# BluetoothMainBoard.net
KiCad netlist of a schematic drawn in EAGLE
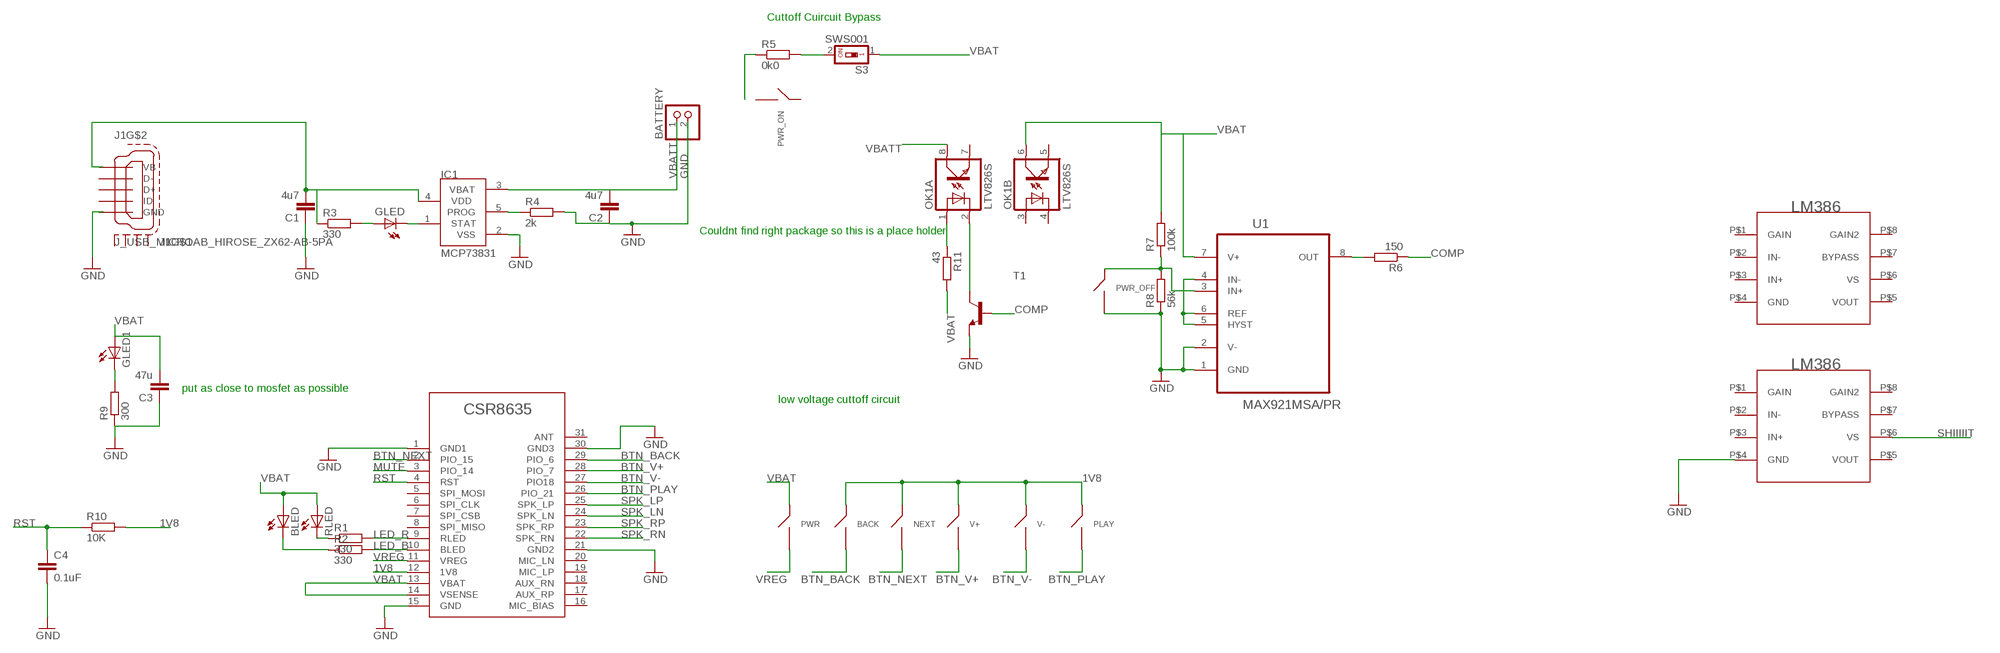
[diagram p0: schematic, sheet 1]

(export (version "E")
  (design (tool "Eeschema 10.0.6"))
  (components
    (comp (ref "BACK")
      (value "TACTILE")
      (footprint "eagle-import:DTSM31N")
      (libsource (lib "eagle-import") (part "TACTILE"))
    )
    (comp (ref "BATTERY")
      (value "PINHD-1X2")
      (footprint "eagle-import:1X02")
      (libsource (lib "eagle-import") (part "PINHD-1X2"))
    )
    (comp (ref "BLED")
      (value "LEDCHIPLED_1206")
      (footprint "eagle-import:CHIPLED_1206")
      (libsource (lib "eagle-import") (part "LEDCHIPLED_1206"))
    )
    (comp (ref "C1")
      (value "4u7")
      (footprint "eagle-import:C0805")
      (libsource (lib "eagle-import") (part "C-EUC0805"))
    )
    (comp (ref "C2")
      (value "4u7")
      (footprint "eagle-import:C0805")
      (libsource (lib "eagle-import") (part "C-EUC0805"))
    )
    (comp (ref "C3")
      (value "47u")
      (footprint "eagle-import:C0805")
      (libsource (lib "eagle-import") (part "C-EUC0805"))
    )
    (comp (ref "C4")
      (value "0.1uF")
      (footprint "eagle-import:C0805")
      (libsource (lib "eagle-import") (part "C-EUC0805"))
    )
    (comp (ref "GLED")
      (value "LEDCHIP-LED0805")
      (footprint "eagle-import:CHIP-LED0805")
      (libsource (lib "eagle-import") (part "led_LEDCHIP-LED0805"))
    )
    (comp (ref "GLED1")
      (value "LEDCHIP-LED0805")
      (footprint "eagle-import:CHIP-LED0805")
      (libsource (lib "eagle-import") (part "led_LEDCHIP-LED0805"))
    )
    (comp (ref "IC1")
      (value "MCP73831")
      (footprint "eagle-import:SOT23-5L")
      (libsource (lib "eagle-import") (part "MCP73831"))
    )
    (comp (ref "J1")
      (value "J_USB_MICROAB_HIROSE_ZX62-AB-5PA")
      (footprint "eagle-import:J_USB_MICROAB_HIROSE_ZX62-AB-5PA")
      (libsource (lib "eagle-import") (part "J_USB_MICROAB_HIROSE_ZX62-AB-5PA"))
    )
    (comp (ref "NEXT")
      (value "TACTILE")
      (footprint "eagle-import:DTSM31N")
      (libsource (lib "eagle-import") (part "TACTILE"))
    )
    (comp (ref "OK1")
      (value "LTV826S")
      (footprint "eagle-import:DIL8-SMD")
      (libsource (lib "eagle-import") (part "LTV826S"))
    )
    (comp (ref "PLAY")
      (value "TACTILE")
      (footprint "eagle-import:DTSM31N")
      (libsource (lib "eagle-import") (part "TACTILE"))
    )
    (comp (ref "PWR")
      (value "TACTILE")
      (footprint "eagle-import:DTSM31N")
      (libsource (lib "eagle-import") (part "TACTILE"))
    )
    (comp (ref "PWR_OFF")
      (value "TACTILE")
      (footprint "eagle-import:DTSM31N")
      (libsource (lib "eagle-import") (part "TACTILE"))
    )
    (comp (ref "PWR_ON")
      (value "TACTILE")
      (footprint "eagle-import:DTSM31N")
      (libsource (lib "eagle-import") (part "TACTILE"))
    )
    (comp (ref "R1")
      (value "330")
      (footprint "eagle-import:R0805W")
      (libsource (lib "eagle-import") (part "R-EU_R0805W"))
    )
    (comp (ref "R2")
      (value "330")
      (footprint "eagle-import:R0805W")
      (libsource (lib "eagle-import") (part "R-EU_R0805W"))
    )
    (comp (ref "R3")
      (value "330")
      (footprint "eagle-import:R0805W")
      (libsource (lib "eagle-import") (part "R-EU_R0805W"))
    )
    (comp (ref "R4")
      (value "2k")
      (footprint "eagle-import:R0805W")
      (libsource (lib "eagle-import") (part "R-EU_R0805W"))
    )
    (comp (ref "R5")
      (value "0k0")
      (footprint "eagle-import:R0805W")
      (libsource (lib "eagle-import") (part "R-EU_R0805W"))
    )
    (comp (ref "R6")
      (value "150")
      (footprint "eagle-import:R0805W")
      (libsource (lib "eagle-import") (part "R-EU_R0805W"))
    )
    (comp (ref "R7")
      (value "100k")
      (footprint "eagle-import:R0805W")
      (libsource (lib "eagle-import") (part "R-EU_R0805W"))
    )
    (comp (ref "R8")
      (value "56k")
      (footprint "eagle-import:R0805W")
      (libsource (lib "eagle-import") (part "R-EU_R0805W"))
    )
    (comp (ref "R9")
      (value "300")
      (footprint "eagle-import:R0805W")
      (libsource (lib "eagle-import") (part "R-EU_R0805W"))
    )
    (comp (ref "R10")
      (value "10K")
      (footprint "eagle-import:R0805W")
      (libsource (lib "eagle-import") (part "R-EU_R0805W"))
    )
    (comp (ref "R11")
      (value "43")
      (footprint "eagle-import:R0805W")
      (libsource (lib "eagle-import") (part "R-EU_R0805W"))
    )
    (comp (ref "RLED")
      (value "LEDCHIPLED_1206")
      (footprint "eagle-import:CHIPLED_1206")
      (libsource (lib "eagle-import") (part "LEDCHIPLED_1206"))
    )
    (comp (ref "S3")
      (value "SWS001")
      (footprint "eagle-import:SMS-001")
      (libsource (lib "eagle-import") (part "SWS001"))
    )
    (comp (ref "T1")
      (value "BC817-16-NPN-SOT23-BEC")
      (footprint "eagle-import:SOT23-BEC")
      (libsource (lib "eagle-import") (part "-NPN-SOT23-BECBC817-16"))
    )
    (comp (ref "U$1")
      (value "CSR8635BRANDON_PINER")
      (footprint "eagle-import:CSR8635PACKAGE")
      (libsource (lib "eagle-import") (part "CSR8635BRANDON_PINER"))
    )
    (comp (ref "U$2")
      (value "LM386")
      (footprint "eagle-import:LM386")
      (libsource (lib "eagle-import") (part "LM386"))
    )
    (comp (ref "U$3")
      (value "LM386")
      (footprint "eagle-import:LM386")
      (libsource (lib "eagle-import") (part "LM386"))
    )
    (comp (ref "U1")
      (value "MAX921MSA/PR")
      (footprint "eagle-import:SOIC127P600X175-8N")
      (libsource (lib "eagle-import") (part "MAX921MSA/PR"))
    )
    (comp (ref "V+")
      (value "TACTILE")
      (footprint "eagle-import:DTSM31N")
      (libsource (lib "eagle-import") (part "TACTILE"))
    )
    (comp (ref "V-")
      (value "TACTILE")
      (footprint "eagle-import:DTSM31N")
      (libsource (lib "eagle-import") (part "TACTILE"))
    )
  )
  (nets
    (net (code "1") (name "/1V8") (class "Default")
      (node (ref "BACK") (pin "P$1") (pinfunction "P$1_P$1") (pintype "bidirectional"))
      (node (ref "NEXT") (pin "P$1") (pinfunction "P$1_P$1") (pintype "bidirectional"))
      (node (ref "PLAY") (pin "P$1") (pinfunction "P$1_P$1") (pintype "bidirectional"))
      (node (ref "R10") (pin "2") (pinfunction "2_2") (pintype "passive"))
      (node (ref "U$1") (pin "12") (pinfunction "1V8_12") (pintype "bidirectional"))
      (node (ref "V+") (pin "P$1") (pinfunction "P$1_P$1") (pintype "bidirectional"))
      (node (ref "V-") (pin "P$1") (pinfunction "P$1_P$1") (pintype "bidirectional"))
    )
    (net (code "2") (name "/BTN_BACK") (class "Default")
      (node (ref "BACK") (pin "P$2") (pinfunction "P$2_P$2") (pintype "bidirectional"))
      (node (ref "U$1") (pin "29") (pinfunction "PIO_6_29") (pintype "bidirectional"))
    )
    (net (code "3") (name "/BTN_NEXT") (class "Default")
      (node (ref "NEXT") (pin "P$2") (pinfunction "P$2_P$2") (pintype "bidirectional"))
      (node (ref "U$1") (pin "2") (pinfunction "PIO_15_2") (pintype "bidirectional"))
    )
    (net (code "4") (name "/BTN_PLAY") (class "Default")
      (node (ref "PLAY") (pin "P$2") (pinfunction "P$2_P$2") (pintype "bidirectional"))
      (node (ref "U$1") (pin "26") (pinfunction "PIO_21_26") (pintype "bidirectional"))
    )
    (net (code "5") (name "/BTN_V+") (class "Default")
      (node (ref "U$1") (pin "28") (pinfunction "PIO_7_28") (pintype "bidirectional"))
      (node (ref "V+") (pin "P$2") (pinfunction "P$2_P$2") (pintype "bidirectional"))
    )
    (net (code "6") (name "/BTN_V-") (class "Default")
      (node (ref "U$1") (pin "27") (pinfunction "PIO18_27") (pintype "bidirectional"))
      (node (ref "V-") (pin "P$2") (pinfunction "P$2_P$2") (pintype "bidirectional"))
    )
    (net (code "7") (name "/COMP") (class "Default")
      (node (ref "R6") (pin "1") (pinfunction "1_1") (pintype "passive"))
      (node (ref "T1") (pin "B") (pinfunction "B_B") (pintype "passive"))
    )
    (net (code "8") (name "/LED_B") (class "Default")
      (node (ref "R2") (pin "2") (pinfunction "2_2") (pintype "passive"))
      (node (ref "U$1") (pin "10") (pinfunction "BLED_10") (pintype "bidirectional"))
    )
    (net (code "9") (name "/LED_R") (class "Default")
      (node (ref "R1") (pin "2") (pinfunction "2_2") (pintype "passive"))
      (node (ref "U$1") (pin "9") (pinfunction "RLED_9") (pintype "bidirectional"))
    )
    (net (code "10") (name "/MUTE") (class "Default")
      (node (ref "U$1") (pin "3") (pinfunction "PIO_14_3") (pintype "bidirectional"))
    )
    (net (code "11") (name "/RST") (class "Default")
      (node (ref "C4") (pin "1") (pinfunction "1_1") (pintype "passive"))
      (node (ref "R10") (pin "1") (pinfunction "1_1") (pintype "passive"))
      (node (ref "U$1") (pin "4") (pinfunction "RST_4") (pintype "bidirectional"))
    )
    (net (code "12") (name "/SHIIIIIT") (class "Default")
      (node (ref "U$2") (pin "P$6") (pinfunction "VS_P$6") (pintype "bidirectional"))
    )
    (net (code "13") (name "/SPK_LN") (class "Default")
      (node (ref "U$1") (pin "24") (pinfunction "SPK_LN_24") (pintype "bidirectional"))
    )
    (net (code "14") (name "/SPK_LP") (class "Default")
      (node (ref "U$1") (pin "25") (pinfunction "SPK_LP_25") (pintype "bidirectional"))
    )
    (net (code "15") (name "/SPK_RN") (class "Default")
      (node (ref "U$1") (pin "22") (pinfunction "SPK_RN_22") (pintype "bidirectional"))
    )
    (net (code "16") (name "/SPK_RP") (class "Default")
      (node (ref "U$1") (pin "23") (pinfunction "SPK_RP_23") (pintype "bidirectional"))
    )
    (net (code "17") (name "/VBAT") (class "Default")
      (node (ref "BLED") (pin "A") (pinfunction "A_A") (pintype "passive"))
      (node (ref "C3") (pin "2") (pinfunction "2_2") (pintype "passive"))
      (node (ref "GLED1") (pin "A") (pinfunction "A_A") (pintype "passive"))
      (node (ref "OK1") (pin "6") (pinfunction "COL_6") (pintype "passive"))
      (node (ref "PWR") (pin "P$1") (pinfunction "P$1_P$1") (pintype "bidirectional"))
      (node (ref "R11") (pin "2") (pinfunction "2_2") (pintype "passive"))
      (node (ref "R7") (pin "2") (pinfunction "2_2") (pintype "passive"))
      (node (ref "RLED") (pin "A") (pinfunction "A_A") (pintype "passive"))
      (node (ref "S3") (pin "1") (pinfunction "1_1") (pintype "passive"))
      (node (ref "U$1") (pin "13") (pinfunction "VBAT_13") (pintype "bidirectional"))
      (node (ref "U$1") (pin "14") (pinfunction "VSENSE_14") (pintype "bidirectional"))
      (node (ref "U1") (pin "7") (pinfunction "V+_7") (pintype "power_in"))
    )
    (net (code "18") (name "/VBATT") (class "Default")
      (node (ref "BATTERY") (pin "1") (pinfunction "1_1") (pintype "passive"))
      (node (ref "C2") (pin "2") (pinfunction "2_2") (pintype "passive"))
      (node (ref "IC1") (pin "3") (pinfunction "VBAT_3") (pintype "bidirectional"))
      (node (ref "OK1") (pin "8") (pinfunction "COL_8") (pintype "passive"))
    )
    (net (code "19") (name "/VREG") (class "Default")
      (node (ref "PWR") (pin "P$2") (pinfunction "P$2_P$2") (pintype "bidirectional"))
      (node (ref "U$1") (pin "11") (pinfunction "VREG_11") (pintype "bidirectional"))
    )
    (net (code "20") (name "GND") (class "Default")
      (node (ref "BATTERY") (pin "2") (pinfunction "2_2") (pintype "passive"))
      (node (ref "C1") (pin "1") (pinfunction "1_1") (pintype "passive"))
      (node (ref "C2") (pin "1") (pinfunction "1_1") (pintype "passive"))
      (node (ref "C3") (pin "1") (pinfunction "1_1") (pintype "passive"))
      (node (ref "C4") (pin "2") (pinfunction "2_2") (pintype "passive"))
      (node (ref "IC1") (pin "2") (pinfunction "VSS_2") (pintype "bidirectional"))
      (node (ref "PWR_OFF") (pin "P$2") (pinfunction "P$2_P$2") (pintype "bidirectional"))
      (node (ref "R4") (pin "2") (pinfunction "2_2") (pintype "passive"))
      (node (ref "R8") (pin "1") (pinfunction "1_1") (pintype "passive"))
      (node (ref "R9") (pin "1") (pinfunction "1_1") (pintype "passive"))
      (node (ref "T1") (pin "E") (pinfunction "E_E") (pintype "passive"))
      (node (ref "U$1") (pin "1") (pinfunction "GND1_1") (pintype "input"))
      (node (ref "U$1") (pin "15") (pinfunction "GND_15") (pintype "bidirectional"))
      (node (ref "U$1") (pin "21") (pinfunction "GND2_21") (pintype "bidirectional"))
      (node (ref "U$1") (pin "30") (pinfunction "GND3_30") (pintype "bidirectional"))
      (node (ref "U$2") (pin "P$4") (pinfunction "GND_P$4") (pintype "bidirectional"))
      (node (ref "U1") (pin "1") (pinfunction "GND_1") (pintype "passive"))
      (node (ref "U1") (pin "2") (pinfunction "V-_2") (pintype "power_in"))
    )
    (net (code "21") (name "Net-(BLED-PadC)") (class "Default")
      (node (ref "BLED") (pin "C") (pinfunction "C_C") (pintype "passive"))
      (node (ref "R2") (pin "1") (pinfunction "1_1") (pintype "passive"))
    )
    (net (code "22") (name "Net-(GLED-PadA)") (class "Default")
      (node (ref "GLED") (pin "A") (pinfunction "A_A") (pintype "passive"))
      (node (ref "R3") (pin "2") (pinfunction "2_2") (pintype "passive"))
    )
    (net (code "23") (name "Net-(GLED1-PadC)") (class "Default")
      (node (ref "GLED1") (pin "C") (pinfunction "C_C") (pintype "passive"))
      (node (ref "R9") (pin "2") (pinfunction "2_2") (pintype "passive"))
    )
    (net (code "24") (name "Net-(IC1-PROG)") (class "Default")
      (node (ref "IC1") (pin "5") (pinfunction "PROG_5") (pintype "bidirectional"))
      (node (ref "R4") (pin "1") (pinfunction "1_1") (pintype "passive"))
    )
    (net (code "25") (name "Net-(IC1-STAT)") (class "Default")
      (node (ref "GLED") (pin "C") (pinfunction "C_C") (pintype "passive"))
      (node (ref "IC1") (pin "1") (pinfunction "STAT_1") (pintype "bidirectional"))
    )
    (net (code "26") (name "Net-(IC1-VDD)") (class "Default")
      (node (ref "C1") (pin "2") (pinfunction "2_2") (pintype "passive"))
      (node (ref "IC1") (pin "4") (pinfunction "VDD_4") (pintype "bidirectional"))
      (node (ref "R3") (pin "1") (pinfunction "1_1") (pintype "passive"))
    )
    (net (code "27") (name "Net-(OK1A-A)") (class "Default")
      (node (ref "OK1") (pin "1") (pinfunction "A_1") (pintype "passive"))
      (node (ref "R11") (pin "1") (pinfunction "1_1") (pintype "passive"))
    )
    (net (code "28") (name "Net-(OK1A-C)") (class "Default")
      (node (ref "OK1") (pin "2") (pinfunction "C_2") (pintype "passive"))
      (node (ref "T1") (pin "C") (pinfunction "C_C") (pintype "passive"))
    )
    (net (code "29") (name "Net-(R1-Pad1)") (class "Default")
      (node (ref "R1") (pin "1") (pinfunction "1_1") (pintype "passive"))
      (node (ref "RLED") (pin "C") (pinfunction "C_C") (pintype "passive"))
    )
    (net (code "30") (name "Net-(R5-Pad2)") (class "Default")
      (node (ref "R5") (pin "2") (pinfunction "2_2") (pintype "passive"))
      (node (ref "S3") (pin "2") (pinfunction "2_2") (pintype "passive"))
    )
    (net (code "31") (name "Net-(U1-HYST)") (class "Default")
      (node (ref "U1") (pin "4") (pinfunction "IN-_4") (pintype "input"))
      (node (ref "U1") (pin "5") (pinfunction "HYST_5") (pintype "input"))
      (node (ref "U1") (pin "6") (pinfunction "REF_6") (pintype "input"))
    )
    (net (code "32") (name "Net-(U1-IN+)") (class "Default")
      (node (ref "PWR_OFF") (pin "P$1") (pinfunction "P$1_P$1") (pintype "bidirectional"))
      (node (ref "R7") (pin "1") (pinfunction "1_1") (pintype "passive"))
      (node (ref "R8") (pin "2") (pinfunction "2_2") (pintype "passive"))
      (node (ref "U1") (pin "3") (pinfunction "IN+_3") (pintype "input"))
    )
    (net (code "33") (name "Net-(U1-OUT)") (class "Default")
      (node (ref "R6") (pin "2") (pinfunction "2_2") (pintype "passive"))
      (node (ref "U1") (pin "8") (pinfunction "OUT_8") (pintype "output"))
    )
    (net (code "34") (name "unconnected-(J1A-S1-PadSHIELD1)") (class "Default")
      (node (ref "J1") (pin "SHIELD1") (pinfunction "S1_SHIELD1") (pintype "passive"))
    )
    (net (code "35") (name "unconnected-(J1A-S2-PadSHIELD2)") (class "Default")
      (node (ref "J1") (pin "SHIELD2") (pinfunction "S2_SHIELD2") (pintype "passive"))
    )
    (net (code "36") (name "unconnected-(J1A-S3-PadSHIELD3)") (class "Default")
      (node (ref "J1") (pin "SHIELD3") (pinfunction "S3_SHIELD3") (pintype "passive"))
    )
    (net (code "37") (name "unconnected-(J1A-S4-PadSHIELD4)") (class "Default")
      (node (ref "J1") (pin "SHIELD4") (pinfunction "S4_SHIELD4") (pintype "passive"))
    )
    (net (code "38") (name "unconnected-(J1B-D+-PadP$3)") (class "Default")
      (node (ref "J1") (pin "P$3") (pinfunction "D+_P$3") (pintype "passive"))
    )
    (net (code "39") (name "unconnected-(J1B-D--PadP$2)") (class "Default")
      (node (ref "J1") (pin "P$2") (pinfunction "D-_P$2") (pintype "passive"))
    )
    (net (code "40") (name "unconnected-(J1B-GND-PadP$5)") (class "Default")
      (node (ref "J1") (pin "P$5") (pinfunction "GND_P$5") (pintype "passive"))
    )
    (net (code "41") (name "unconnected-(J1B-ID-PadP$4)") (class "Default")
      (node (ref "J1") (pin "P$4") (pinfunction "ID_P$4") (pintype "passive"))
    )
    (net (code "42") (name "unconnected-(J1B-VB-PadP$1)") (class "Default")
      (node (ref "J1") (pin "P$1") (pinfunction "VB_P$1") (pintype "passive"))
    )
    (net (code "43") (name "unconnected-(OK1A-EMIT-Pad7)") (class "Default")
      (node (ref "OK1") (pin "7") (pinfunction "EMIT_7") (pintype "passive"))
    )
    (net (code "44") (name "unconnected-(OK1B-A-Pad3)") (class "Default")
      (node (ref "OK1") (pin "3") (pinfunction "A_3") (pintype "passive"))
    )
    (net (code "45") (name "unconnected-(OK1B-C-Pad4)") (class "Default")
      (node (ref "OK1") (pin "4") (pinfunction "C_4") (pintype "passive"))
    )
    (net (code "46") (name "unconnected-(OK1B-EMIT-Pad5)") (class "Default")
      (node (ref "OK1") (pin "5") (pinfunction "EMIT_5") (pintype "passive"))
    )
    (net (code "47") (name "unconnected-(PWR_ON-PadP$1)") (class "Default")
      (node (ref "PWR_ON") (pin "P$1") (pinfunction "P$1_P$1") (pintype "bidirectional"))
    )
    (net (code "48") (name "unconnected-(PWR_ON-PadP$2)") (class "Default")
      (node (ref "PWR_ON") (pin "P$2") (pinfunction "P$2_P$2") (pintype "bidirectional"))
    )
    (net (code "49") (name "unconnected-(R5-Pad1)") (class "Default")
      (node (ref "R5") (pin "1") (pinfunction "1_1") (pintype "passive"))
    )
    (net (code "50") (name "unconnected-(U$1-ANT-Pad31)") (class "Default")
      (node (ref "U$1") (pin "31") (pinfunction "ANT_31") (pintype "bidirectional"))
    )
    (net (code "51") (name "unconnected-(U$1-AUX_RN-Pad18)") (class "Default")
      (node (ref "U$1") (pin "18") (pinfunction "AUX_RN_18") (pintype "bidirectional"))
    )
    (net (code "52") (name "unconnected-(U$1-AUX_RP-Pad17)") (class "Default")
      (node (ref "U$1") (pin "17") (pinfunction "AUX_RP_17") (pintype "bidirectional"))
    )
    (net (code "53") (name "unconnected-(U$1-MIC_BIAS-Pad16)") (class "Default")
      (node (ref "U$1") (pin "16") (pinfunction "MIC_BIAS_16") (pintype "bidirectional"))
    )
    (net (code "54") (name "unconnected-(U$1-MIC_LN-Pad20)") (class "Default")
      (node (ref "U$1") (pin "20") (pinfunction "MIC_LN_20") (pintype "bidirectional"))
    )
    (net (code "55") (name "unconnected-(U$1-MIC_LP-Pad19)") (class "Default")
      (node (ref "U$1") (pin "19") (pinfunction "MIC_LP_19") (pintype "bidirectional"))
    )
    (net (code "56") (name "unconnected-(U$1-SPI_CLK-Pad6)") (class "Default")
      (node (ref "U$1") (pin "6") (pinfunction "SPI_CLK_6") (pintype "bidirectional"))
    )
    (net (code "57") (name "unconnected-(U$1-SPI_CSB-Pad7)") (class "Default")
      (node (ref "U$1") (pin "7") (pinfunction "SPI_CSB_7") (pintype "bidirectional"))
    )
    (net (code "58") (name "unconnected-(U$1-SPI_MISO-Pad8)") (class "Default")
      (node (ref "U$1") (pin "8") (pinfunction "SPI_MISO_8") (pintype "bidirectional"))
    )
    (net (code "59") (name "unconnected-(U$1-SPI_MOSI-Pad5)") (class "Default")
      (node (ref "U$1") (pin "5") (pinfunction "SPI_MOSI_5") (pintype "bidirectional"))
    )
    (net (code "60") (name "unconnected-(U$2-BYPASS-PadP$7)") (class "Default")
      (node (ref "U$2") (pin "P$7") (pinfunction "BYPASS_P$7") (pintype "bidirectional"))
    )
    (net (code "61") (name "unconnected-(U$2-GAIN-PadP$1)") (class "Default")
      (node (ref "U$2") (pin "P$1") (pinfunction "GAIN_P$1") (pintype "bidirectional"))
    )
    (net (code "62") (name "unconnected-(U$2-GAIN2-PadP$8)") (class "Default")
      (node (ref "U$2") (pin "P$8") (pinfunction "GAIN2_P$8") (pintype "bidirectional"))
    )
    (net (code "63") (name "unconnected-(U$2-IN+-PadP$3)") (class "Default")
      (node (ref "U$2") (pin "P$3") (pinfunction "IN+_P$3") (pintype "bidirectional"))
    )
    (net (code "64") (name "unconnected-(U$2-IN--PadP$2)") (class "Default")
      (node (ref "U$2") (pin "P$2") (pinfunction "IN-_P$2") (pintype "bidirectional"))
    )
    (net (code "65") (name "unconnected-(U$2-VOUT-PadP$5)") (class "Default")
      (node (ref "U$2") (pin "P$5") (pinfunction "VOUT_P$5") (pintype "bidirectional"))
    )
    (net (code "66") (name "unconnected-(U$3-BYPASS-PadP$7)") (class "Default")
      (node (ref "U$3") (pin "P$7") (pinfunction "BYPASS_P$7") (pintype "bidirectional"))
    )
    (net (code "67") (name "unconnected-(U$3-GAIN-PadP$1)") (class "Default")
      (node (ref "U$3") (pin "P$1") (pinfunction "GAIN_P$1") (pintype "bidirectional"))
    )
    (net (code "68") (name "unconnected-(U$3-GAIN2-PadP$8)") (class "Default")
      (node (ref "U$3") (pin "P$8") (pinfunction "GAIN2_P$8") (pintype "bidirectional"))
    )
    (net (code "69") (name "unconnected-(U$3-GND-PadP$4)") (class "Default")
      (node (ref "U$3") (pin "P$4") (pinfunction "GND_P$4") (pintype "bidirectional"))
    )
    (net (code "70") (name "unconnected-(U$3-IN+-PadP$3)") (class "Default")
      (node (ref "U$3") (pin "P$3") (pinfunction "IN+_P$3") (pintype "bidirectional"))
    )
    (net (code "71") (name "unconnected-(U$3-IN--PadP$2)") (class "Default")
      (node (ref "U$3") (pin "P$2") (pinfunction "IN-_P$2") (pintype "bidirectional"))
    )
    (net (code "72") (name "unconnected-(U$3-VOUT-PadP$5)") (class "Default")
      (node (ref "U$3") (pin "P$5") (pinfunction "VOUT_P$5") (pintype "bidirectional"))
    )
    (net (code "73") (name "unconnected-(U$3-VS-PadP$6)") (class "Default")
      (node (ref "U$3") (pin "P$6") (pinfunction "VS_P$6") (pintype "bidirectional"))
    )
  )
)
